# resolver_ad2s1210.net
KiCad netlist of a schematic drawn in Altium Designer
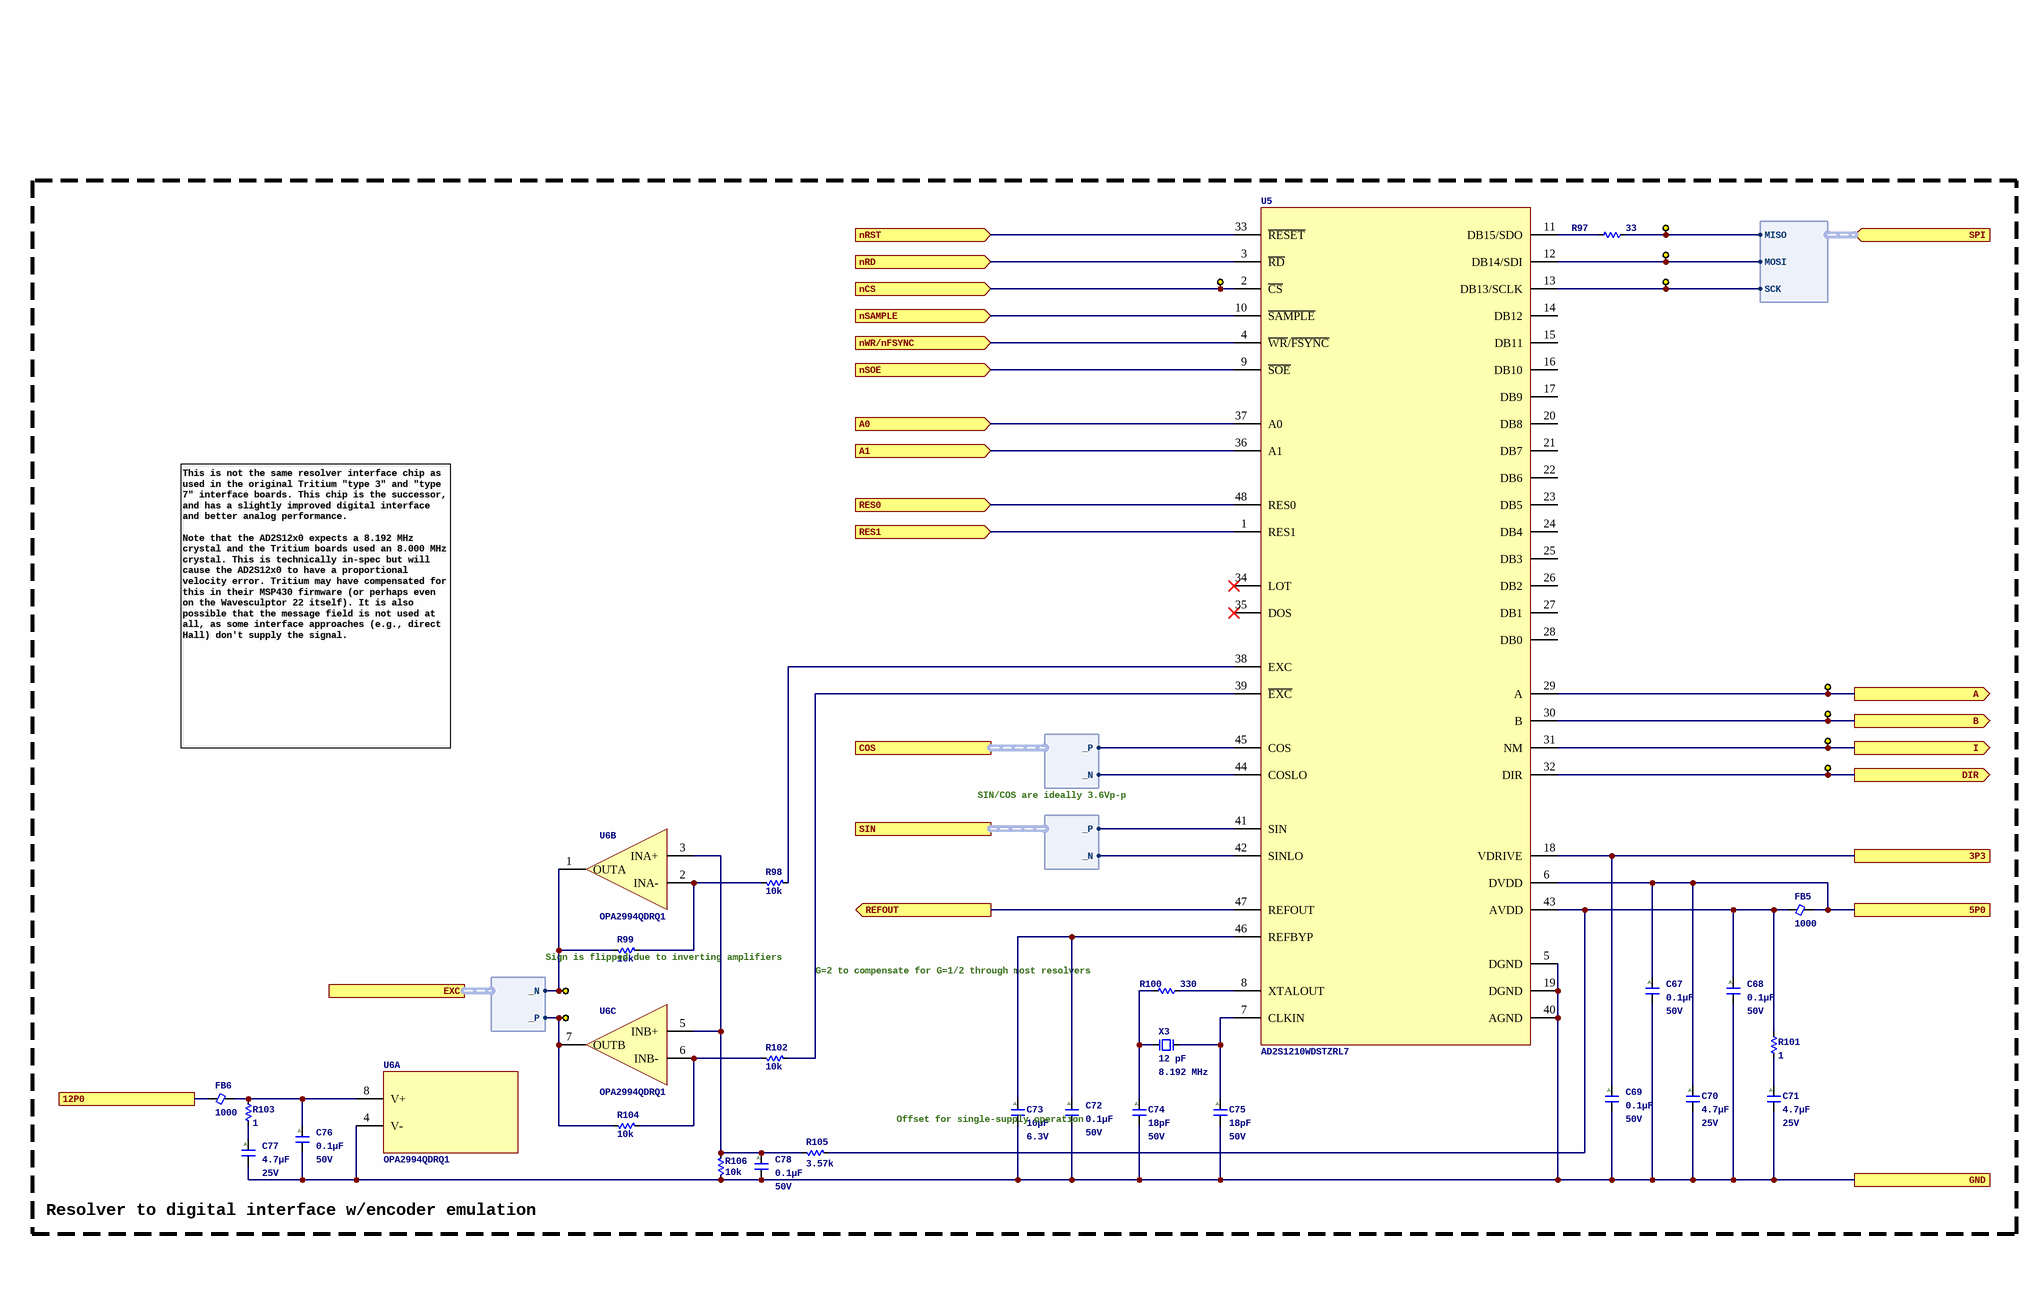
[diagram p0: resolver_ad2s1210.SchDoc]

(export (version "E")
  (design (tool "Eeschema 10.0.6"))
  (components
    (comp (ref "C67")
      (value "CGA2B3X7R1H104M050BB")
      (footprint "C0402_0.55MM")
      (description "CAP CER 0.1UF 50V X7R 0402")
      (fields
        (field (name "CAPACITANCE") "0.1µF")
        (field (name "VOLTAGE - RATED") "50V")
        (field (name "TOLERANCE") "±20%")
        (field (name "MANUFACTURER") "TDK Corporation")
      )
      (libsource (lib "sscp") (part "__template_cap_auto"))
    )
    (comp (ref "C68")
      (value "CGA2B3X7R1H104M050BB")
      (footprint "C0402_0.55MM")
      (description "CAP CER 0.1UF 50V X7R 0402")
      (fields
        (field (name "CAPACITANCE") "0.1µF")
        (field (name "VOLTAGE - RATED") "50V")
        (field (name "TOLERANCE") "±20%")
        (field (name "MANUFACTURER") "TDK Corporation")
      )
      (libsource (lib "sscp") (part "__template_cap_auto"))
    )
    (comp (ref "C69")
      (value "CGA2B3X7R1H104M050BB")
      (footprint "C0402_0.55MM")
      (description "CAP CER 0.1UF 50V X7R 0402")
      (fields
        (field (name "CAPACITANCE") "0.1µF")
        (field (name "VOLTAGE - RATED") "50V")
        (field (name "TOLERANCE") "±20%")
        (field (name "MANUFACTURER") "TDK Corporation")
      )
      (libsource (lib "sscp") (part "__template_cap_auto"))
    )
    (comp (ref "C70")
      (value "CGA4J1X7R1E475K125AC")
      (footprint "C0805_1.45MM")
      (description "CAP CER 4.7UF 25V X7R 0805")
      (fields
        (field (name "CAPACITANCE") "4.7µF")
        (field (name "VOLTAGE - RATED") "25V")
        (field (name "TOLERANCE") "±10%")
        (field (name "MANUFACTURER") "TDK Corporation")
      )
      (libsource (lib "sscp") (part "__template_cap_auto"))
    )
    (comp (ref "C71")
      (value "CGA4J1X7R1E475K125AC")
      (footprint "C0805_1.45MM")
      (description "CAP CER 4.7UF 25V X7R 0805")
      (fields
        (field (name "CAPACITANCE") "4.7µF")
        (field (name "VOLTAGE - RATED") "25V")
        (field (name "TOLERANCE") "±10%")
        (field (name "MANUFACTURER") "TDK Corporation")
      )
      (libsource (lib "sscp") (part "__template_cap_auto"))
    )
    (comp (ref "C72")
      (value "CGA2B3X7R1H104M050BB")
      (footprint "C0402_0.55MM")
      (description "CAP CER 0.1UF 50V X7R 0402")
      (fields
        (field (name "CAPACITANCE") "0.1µF")
        (field (name "VOLTAGE - RATED") "50V")
        (field (name "TOLERANCE") "±20%")
        (field (name "MANUFACTURER") "TDK Corporation")
      )
      (libsource (lib "sscp") (part "__template_cap_auto"))
    )
    (comp (ref "C73")
      (value "CGA4J1X7R0J106M125AC")
      (footprint "C0805_1.45MM")
      (description "CAP CER 10UF 6.3V X7R 0805")
      (fields
        (field (name "CAPACITANCE") "10µF")
        (field (name "VOLTAGE - RATED") "6.3V")
        (field (name "TOLERANCE") "±20%")
        (field (name "MANUFACTURER") "TDK Corporation")
      )
      (libsource (lib "sscp") (part "__template_cap_auto"))
    )
    (comp (ref "C74")
      (value "CGA2B2C0G1H180J050BA")
      (footprint "C0402_0.55MM")
      (description "CAP CER 18PF 50V C0G 0402")
      (fields
        (field (name "CAPACITANCE") "18pF")
        (field (name "VOLTAGE - RATED") "50V")
        (field (name "TOLERANCE") "±5%")
        (field (name "MANUFACTURER") "TDK Corporation")
      )
      (libsource (lib "sscp") (part "__template_cap_auto"))
    )
    (comp (ref "C75")
      (value "CGA2B2C0G1H180J050BA")
      (footprint "C0402_0.55MM")
      (description "CAP CER 18PF 50V C0G 0402")
      (fields
        (field (name "CAPACITANCE") "18pF")
        (field (name "VOLTAGE - RATED") "50V")
        (field (name "TOLERANCE") "±5%")
        (field (name "MANUFACTURER") "TDK Corporation")
      )
      (libsource (lib "sscp") (part "__template_cap_auto"))
    )
    (comp (ref "C76")
      (value "CGA2B3X7R1H104M050BB")
      (footprint "C0402_0.55MM")
      (description "CAP CER 0.1UF 50V X7R 0402")
      (fields
        (field (name "CAPACITANCE") "0.1µF")
        (field (name "VOLTAGE - RATED") "50V")
        (field (name "TOLERANCE") "±20%")
        (field (name "MANUFACTURER") "TDK Corporation")
      )
      (libsource (lib "sscp") (part "__template_cap_auto"))
    )
    (comp (ref "C77")
      (value "CGA4J1X7R1E475K125AC")
      (footprint "C0805_1.45MM")
      (description "CAP CER 4.7UF 25V X7R 0805")
      (fields
        (field (name "CAPACITANCE") "4.7µF")
        (field (name "VOLTAGE - RATED") "25V")
        (field (name "TOLERANCE") "±10%")
        (field (name "MANUFACTURER") "TDK Corporation")
      )
      (libsource (lib "sscp") (part "__template_cap_auto"))
    )
    (comp (ref "C78")
      (value "CGA2B3X7R1H104M050BB")
      (footprint "C0402_0.55MM")
      (description "CAP CER 0.1UF 50V X7R 0402")
      (fields
        (field (name "CAPACITANCE") "0.1µF")
        (field (name "VOLTAGE - RATED") "50V")
        (field (name "TOLERANCE") "±20%")
        (field (name "MANUFACTURER") "TDK Corporation")
      )
      (libsource (lib "sscp") (part "__template_cap_auto"))
    )
    (comp (ref "FB5")
      (value "MPZ2012S102AT000")
      (footprint "FB0805_1.05MM")
      (description "FERRITE BEAD 1 KOHM 0805 1LN")
      (fields
        (field (name "IMPEDANCE (OHMS @ 100MHZ)") "1000")
        (field (name "MANUFACTURER") "TDK Corporation")
      )
      (libsource (lib "sscp") (part "__template_ferrite"))
    )
    (comp (ref "FB6")
      (value "MPZ2012S102AT000")
      (footprint "FB0805_1.05MM")
      (description "FERRITE BEAD 1 KOHM 0805 1LN")
      (fields
        (field (name "IMPEDANCE (OHMS @ 100MHZ)") "1000")
        (field (name "MANUFACTURER") "TDK Corporation")
      )
      (libsource (lib "sscp") (part "__template_ferrite"))
    )
    (comp (ref "R97")
      (value "ERJ-2RKF33R0X")
      (footprint "R0402_0.40MM")
      (description "RES SMD 33 OHM 1% 1/10W 0402")
      (fields
        (field (name "RESISTANCE") "33")
        (field (name "TOLERANCE") "±1%")
        (field (name "MANUFACTURER") "Panasonic Electronic Components")
      )
      (libsource (lib "sscp") (part "__template_resistor"))
    )
    (comp (ref "R98")
      (value "ERJ-2RKF1002X")
      (footprint "R0402_0.40MM")
      (description "RES SMD 10K OHM 1% 1/10W 0402")
      (fields
        (field (name "RESISTANCE") "10k")
        (field (name "TOLERANCE") "±1%")
        (field (name "MANUFACTURER") "Panasonic Electronic Components")
      )
      (libsource (lib "sscp") (part "__template_resistor"))
    )
    (comp (ref "R99")
      (value "ERJ-2RKF1002X")
      (footprint "R0402_0.40MM")
      (description "RES SMD 10K OHM 1% 1/10W 0402")
      (fields
        (field (name "RESISTANCE") "10k")
        (field (name "TOLERANCE") "±1%")
        (field (name "MANUFACTURER") "Panasonic Electronic Components")
      )
      (libsource (lib "sscp") (part "__template_resistor"))
    )
    (comp (ref "R100")
      (value "ERJ-PA2F3300X")
      (footprint "R0402_0.40MM")
      (description "RES SMD 330 OHM 1% 1/5W 0402")
      (fields
        (field (name "RESISTANCE") "330")
        (field (name "TOLERANCE") "±1%")
        (field (name "MANUFACTURER") "Panasonic Electronic Components")
      )
      (libsource (lib "sscp") (part "__template_resistor"))
    )
    (comp (ref "R101")
      (value "ERJ-2BQF1R0X")
      (footprint "R0402_0.40MM")
      (description "RES SMD 1 OHM 1% 1/6W 0402")
      (fields
        (field (name "RESISTANCE") "1")
        (field (name "TOLERANCE") "±1%")
        (field (name "MANUFACTURER") "Panasonic Electronic Components")
      )
      (libsource (lib "sscp") (part "__template_resistor"))
    )
    (comp (ref "R102")
      (value "ERJ-2RKF1002X")
      (footprint "R0402_0.40MM")
      (description "RES SMD 10K OHM 1% 1/10W 0402")
      (fields
        (field (name "RESISTANCE") "10k")
        (field (name "TOLERANCE") "±1%")
        (field (name "MANUFACTURER") "Panasonic Electronic Components")
      )
      (libsource (lib "sscp") (part "__template_resistor"))
    )
    (comp (ref "R103")
      (value "ERJ-2BQF1R0X")
      (footprint "R0402_0.40MM")
      (description "RES SMD 1 OHM 1% 1/6W 0402")
      (fields
        (field (name "RESISTANCE") "1")
        (field (name "TOLERANCE") "±1%")
        (field (name "MANUFACTURER") "Panasonic Electronic Components")
      )
      (libsource (lib "sscp") (part "__template_resistor"))
    )
    (comp (ref "R104")
      (value "ERJ-2RKF1002X")
      (footprint "R0402_0.40MM")
      (description "RES SMD 10K OHM 1% 1/10W 0402")
      (fields
        (field (name "RESISTANCE") "10k")
        (field (name "TOLERANCE") "±1%")
        (field (name "MANUFACTURER") "Panasonic Electronic Components")
      )
      (libsource (lib "sscp") (part "__template_resistor"))
    )
    (comp (ref "R105")
      (value "ERJ-2RKF3571X")
      (footprint "R0402_0.40MM")
      (description "RES SMD 3.57K OHM 1% 1/10W 0402")
      (fields
        (field (name "RESISTANCE") "3.57k")
        (field (name "TOLERANCE") "±1%")
        (field (name "MANUFACTURER") "Panasonic Electronic Components")
      )
      (libsource (lib "sscp") (part "__template_resistor"))
    )
    (comp (ref "R106")
      (value "ERJ-2RKF1002X")
      (footprint "R0402_0.40MM")
      (description "RES SMD 10K OHM 1% 1/10W 0402")
      (fields
        (field (name "RESISTANCE") "10k")
        (field (name "TOLERANCE") "±1%")
        (field (name "MANUFACTURER") "Panasonic Electronic Components")
      )
      (libsource (lib "sscp") (part "__template_resistor"))
    )
    (comp (ref "TP5")
      (value "~")
      (footprint "TP_GRABBY")
      (description "EMBEDDED TEST POINT FOR SALEAE TEST CLIPS")
      (libsource (lib "SSCP") (part "TEST_GRABBER"))
    )
    (comp (ref "TP6")
      (value "~")
      (footprint "TP_GRABBY")
      (description "EMBEDDED TEST POINT FOR SALEAE TEST CLIPS")
      (libsource (lib "SSCP") (part "TEST_GRABBER"))
    )
    (comp (ref "TP7")
      (value "~")
      (footprint "TP_GRABBY")
      (description "EMBEDDED TEST POINT FOR SALEAE TEST CLIPS")
      (libsource (lib "SSCP") (part "TEST_GRABBER"))
    )
    (comp (ref "TP18")
      (value "~")
      (footprint "TP_GRABBY")
      (description "EMBEDDED TEST POINT FOR SALEAE TEST CLIPS")
      (libsource (lib "SSCP") (part "TEST_GRABBER"))
    )
    (comp (ref "TP19")
      (value "~")
      (footprint "TP_GRABBY")
      (description "EMBEDDED TEST POINT FOR SALEAE TEST CLIPS")
      (libsource (lib "SSCP") (part "TEST_GRABBER"))
    )
    (comp (ref "TP20")
      (value "~")
      (footprint "TP_GRABBY")
      (description "EMBEDDED TEST POINT FOR SALEAE TEST CLIPS")
      (libsource (lib "SSCP") (part "TEST_GRABBER"))
    )
    (comp (ref "TP21")
      (value "~")
      (footprint "TP_GRABBY")
      (description "EMBEDDED TEST POINT FOR SALEAE TEST CLIPS")
      (libsource (lib "SSCP") (part "TEST_GRABBER"))
    )
    (comp (ref "TP22")
      (value "~")
      (footprint "TP_GRABBY")
      (description "EMBEDDED TEST POINT FOR SALEAE TEST CLIPS")
      (libsource (lib "SSCP") (part "TEST_GRABBER"))
    )
    (comp (ref "TP23")
      (value "RH-5002")
      (footprint "TP_RH-5002")
      (description "THT white clip turret")
      (fields (field (name "MANUFACTURER") "ronghe"))
      (libsource (lib "sscp") (part "__template_testpoint"))
    )
    (comp (ref "TP24")
      (value "RH-5002")
      (footprint "TP_RH-5002")
      (description "THT white clip turret")
      (fields (field (name "MANUFACTURER") "ronghe"))
      (libsource (lib "sscp") (part "__template_testpoint"))
    )
    (comp (ref "U5")
      (value "AD2S1210WDSTZRL7")
      (footprint "48TQFP7")
      (description "Synchro or Resolver to Digital Converter, PQFP44")
      (fields (field (name "MANUFACTURER") "Analog Devices"))
      (libsource (lib "SSCP") (part "RESOLVER_AD2S1210WDSTZ"))
    )
    (comp (ref "U6")
      (value "OPA2994QDRQ1")
      (footprint "8SOIC150")
      (description "Automotive, dual, 24V 25MHz high-output-current (150 mA) operational amplifier 8-SOIC -40 to 125")
      (fields (field (name "MANUFACTURER") "Texas Instruments"))
      (libsource (lib "") (part "OPAMP_OPA2994QDRQ1_1"))
    )
    (comp (ref "X3")
      (value "ECS-81.92-12-30Q-EN-TR")
      (footprint "XTAL_ECX-53Q")
      (description "Parallel - Fundamental Quartz Crystal, 8.192MHz Nom")
      (fields
        (field (name "MANUFACTURER") "ECS International")
        (field (name "LOAD CAPACITANCE") "12 pF")
        (field (name "FREQUENCY") "8.192 MHz")
      )
      (libsource (lib "SSCP") (part "XTAL_ECS-81.92-12-30Q-EN-TR"))
    )
  )
  (nets
    (net (code "3") (name "/3P3") (class "Default")
      (node (ref "C69") (pin "1") (pintype "passive"))
      (node (ref "U5") (pin "18") (pinfunction "VDRIVE_18") (pintype "passive"))
    )
    (net (code "4") (name "/5P0") (class "Default")
      (node (ref "C67") (pin "1") (pintype "passive"))
      (node (ref "C70") (pin "1") (pintype "passive"))
      (node (ref "FB5") (pin "2") (pintype "passive"))
      (node (ref "U5") (pin "6") (pinfunction "DVDD_6") (pintype "passive"))
    )
    (net (code "5") (name "/12P0") (class "Default") (node (ref "FB6") (pin "1") (pintype "passive")))
    (net (code "6") (name "/A") (class "Default")
      (node (ref "TP18") (pin "1") (pintype "passive"))
      (node (ref "U5") (pin "29") (pinfunction "A_29") (pintype "passive"))
    )
    (net (code "7") (name "/A0") (class "Default")
      (node (ref "U5") (pin "37") (pinfunction "A0_37") (pintype "passive"))
    )
    (net (code "8") (name "/A1") (class "Default")
      (node (ref "U5") (pin "36") (pinfunction "A1_36") (pintype "passive"))
    )
    (net (code "9") (name "/B") (class "Default")
      (node (ref "TP19") (pin "1") (pintype "passive"))
      (node (ref "U5") (pin "30") (pinfunction "B_30") (pintype "passive"))
    )
    (net (code "10") (name "/DIR") (class "Default")
      (node (ref "TP21") (pin "1") (pintype "passive"))
      (node (ref "U5") (pin "32") (pinfunction "DIR_32") (pintype "passive"))
    )
    (net (code "11") (name "/GND") (class "Default")
      (node (ref "C67") (pin "2") (pintype "passive"))
      (node (ref "C68") (pin "2") (pintype "passive"))
      (node (ref "C69") (pin "2") (pintype "passive"))
      (node (ref "C70") (pin "2") (pintype "passive"))
      (node (ref "C71") (pin "2") (pintype "passive"))
      (node (ref "C72") (pin "2") (pintype "passive"))
      (node (ref "C73") (pin "2") (pintype "passive"))
      (node (ref "C74") (pin "2") (pintype "passive"))
      (node (ref "C75") (pin "2") (pintype "passive"))
      (node (ref "C76") (pin "2") (pintype "passive"))
      (node (ref "C77") (pin "2") (pintype "passive"))
      (node (ref "C78") (pin "2") (pintype "passive"))
      (node (ref "R106") (pin "2") (pintype "passive"))
      (node (ref "U5") (pin "19") (pinfunction "DGND_19") (pintype "passive"))
      (node (ref "U5") (pin "40") (pinfunction "AGND_40") (pintype "passive"))
      (node (ref "U5") (pin "5") (pinfunction "DGND_5") (pintype "passive"))
      (node (ref "U6") (pin "4") (pinfunction "V-_4") (pintype "passive"))
    )
    (net (code "12") (name "/I") (class "Default")
      (node (ref "TP20") (pin "1") (pintype "passive"))
      (node (ref "U5") (pin "31") (pinfunction "NM_31") (pintype "passive"))
    )
    (net (code "13") (name "/MISO") (class "Default")
      (node (ref "R97") (pin "1") (pintype "passive"))
      (node (ref "TP5") (pin "1") (pintype "passive"))
    )
    (net (code "14") (name "/MOSI") (class "Default")
      (node (ref "TP6") (pin "1") (pintype "passive"))
      (node (ref "U5") (pin "12") (pinfunction "DB14/SDI_12") (pintype "passive"))
    )
    (net (code "15") (name "/REFOUT") (class "Default")
      (node (ref "U5") (pin "47") (pinfunction "REFOUT_47") (pintype "passive"))
    )
    (net (code "16") (name "/RES0") (class "Default")
      (node (ref "U5") (pin "48") (pinfunction "RES0_48") (pintype "passive"))
    )
    (net (code "17") (name "/RES1") (class "Default")
      (node (ref "U5") (pin "1") (pinfunction "RES1_1") (pintype "passive"))
    )
    (net (code "18") (name "/SCK") (class "Default")
      (node (ref "TP7") (pin "1") (pintype "passive"))
      (node (ref "U5") (pin "13") (pinfunction "DB13/SCLK_13") (pintype "passive"))
    )
    (net (code "19") (name "/nCS") (class "Default")
      (node (ref "TP22") (pin "1") (pintype "passive"))
      (node (ref "U5") (pin "2") (pinfunction "~{CS}_2") (pintype "passive"))
    )
    (net (code "20") (name "/nRD") (class "Default")
      (node (ref "U5") (pin "3") (pinfunction "~{RD}_3") (pintype "passive"))
    )
    (net (code "21") (name "/nRST") (class "Default")
      (node (ref "U5") (pin "33") (pinfunction "~{RESET}_33") (pintype "passive"))
    )
    (net (code "22") (name "/nSAMPLE") (class "Default")
      (node (ref "U5") (pin "10") (pinfunction "~{SAMPLE}_10") (pintype "passive"))
    )
    (net (code "23") (name "/nSOE") (class "Default")
      (node (ref "U5") (pin "9") (pinfunction "~{SOE}_9") (pintype "passive"))
    )
    (net (code "24") (name "/nWR{slash}nFSYNC") (class "Default")
      (node (ref "U5") (pin "4") (pinfunction "~{WR}/~{FSYNC}_4") (pintype "passive"))
    )
    (net (code "27") (name "Net-(C71-Pad1)") (class "Default")
      (node (ref "C71") (pin "1") (pintype "passive"))
      (node (ref "R101") (pin "1") (pintype "passive"))
    )
    (net (code "28") (name "Net-(C74-Pad1)") (class "Default")
      (node (ref "C74") (pin "1") (pintype "passive"))
      (node (ref "R100") (pin "1") (pintype "passive"))
      (node (ref "X3") (pin "1") (pinfunction "1_1") (pintype "passive"))
    )
    (net (code "29") (name "Net-(C77-Pad1)") (class "Default")
      (node (ref "C77") (pin "1") (pintype "passive"))
      (node (ref "R103") (pin "1") (pintype "passive"))
    )
    (net (code "30") (name "Net-(U5-AVDD)") (class "Default")
      (node (ref "C68") (pin "1") (pintype "passive"))
      (node (ref "FB5") (pin "1") (pintype "passive"))
      (node (ref "R101") (pin "2") (pintype "passive"))
      (node (ref "R105") (pin "2") (pintype "passive"))
      (node (ref "U5") (pin "43") (pinfunction "AVDD_43") (pintype "passive"))
    )
    (net (code "31") (name "Net-(U5-CLKIN)") (class "Default")
      (node (ref "C75") (pin "1") (pintype "passive"))
      (node (ref "U5") (pin "7") (pinfunction "CLKIN_7") (pintype "passive"))
      (node (ref "X3") (pin "2") (pinfunction "2_2") (pintype "passive"))
    )
    (net (code "32") (name "Net-(U5-DB15{slash}SDO)") (class "Default")
      (node (ref "R97") (pin "2") (pintype "passive"))
      (node (ref "U5") (pin "11") (pinfunction "DB15/SDO_11") (pintype "passive"))
    )
    (net (code "33") (name "Net-(U5-EXC)") (class "Default")
      (node (ref "R98") (pin "2") (pintype "passive"))
      (node (ref "U5") (pin "38") (pinfunction "EXC_38") (pintype "passive"))
    )
    (net (code "34") (name "Net-(U5-REFBYP)") (class "Default")
      (node (ref "C72") (pin "1") (pintype "passive"))
      (node (ref "C73") (pin "1") (pintype "passive"))
      (node (ref "U5") (pin "46") (pinfunction "REFBYP_46") (pintype "passive"))
    )
    (net (code "35") (name "Net-(U5-XTALOUT)") (class "Default")
      (node (ref "R100") (pin "2") (pintype "passive"))
      (node (ref "U5") (pin "8") (pinfunction "XTALOUT_8") (pintype "passive"))
    )
    (net (code "36") (name "Net-(U5-~{EXC})") (class "Default")
      (node (ref "R102") (pin "2") (pintype "passive"))
      (node (ref "U5") (pin "39") (pinfunction "~{EXC}_39") (pintype "passive"))
    )
    (net (code "37") (name "Net-(U6A-V+)") (class "Default")
      (node (ref "C76") (pin "1") (pintype "passive"))
      (node (ref "FB6") (pin "2") (pintype "passive"))
      (node (ref "R103") (pin "2") (pintype "passive"))
      (node (ref "U6") (pin "8") (pinfunction "V+_8") (pintype "passive"))
    )
    (net (code "38") (name "Net-(U6B-INA+)") (class "Default")
      (node (ref "C78") (pin "1") (pintype "passive"))
      (node (ref "R105") (pin "1") (pintype "passive"))
      (node (ref "R106") (pin "1") (pintype "passive"))
      (node (ref "U6") (pin "3") (pinfunction "INA+_3") (pintype "passive"))
      (node (ref "U6") (pin "5") (pinfunction "INB+_5") (pintype "passive"))
    )
    (net (code "39") (name "Net-(U6B-INA-)") (class "Default")
      (node (ref "R98") (pin "1") (pintype "passive"))
      (node (ref "R99") (pin "2") (pintype "passive"))
      (node (ref "U6") (pin "2") (pinfunction "INA-_2") (pintype "passive"))
    )
    (net (code "40") (name "Net-(U6B-OUTA)") (class "Default")
      (node (ref "R99") (pin "1") (pintype "passive"))
      (node (ref "TP23") (pin "1") (pintype "passive"))
      (node (ref "U6") (pin "1") (pinfunction "OUTA_1") (pintype "passive"))
    )
    (net (code "41") (name "Net-(U6C-INB-)") (class "Default")
      (node (ref "R102") (pin "1") (pintype "passive"))
      (node (ref "R104") (pin "2") (pintype "passive"))
      (node (ref "U6") (pin "6") (pinfunction "INB-_6") (pintype "passive"))
    )
    (net (code "42") (name "Net-(U6C-OUTB)") (class "Default")
      (node (ref "R104") (pin "1") (pintype "passive"))
      (node (ref "TP24") (pin "1") (pintype "passive"))
      (node (ref "U6") (pin "7") (pinfunction "OUTB_7") (pintype "passive"))
    )
    (net (code "43") (name "unconnected-(U5-COS-Pad45)") (class "Default")
      (node (ref "U5") (pin "45") (pinfunction "COS_45") (pintype "passive"))
    )
    (net (code "44") (name "unconnected-(U5-COSLO-Pad44)") (class "Default")
      (node (ref "U5") (pin "44") (pinfunction "COSLO_44") (pintype "passive"))
    )
    (net (code "45") (name "unconnected-(U5-DB0-Pad28)") (class "Default")
      (node (ref "U5") (pin "28") (pinfunction "DB0_28") (pintype "passive"))
    )
    (net (code "46") (name "unconnected-(U5-DB1-Pad27)") (class "Default")
      (node (ref "U5") (pin "27") (pinfunction "DB1_27") (pintype "passive"))
    )
    (net (code "47") (name "unconnected-(U5-DB2-Pad26)") (class "Default")
      (node (ref "U5") (pin "26") (pinfunction "DB2_26") (pintype "passive"))
    )
    (net (code "48") (name "unconnected-(U5-DB3-Pad25)") (class "Default")
      (node (ref "U5") (pin "25") (pinfunction "DB3_25") (pintype "passive"))
    )
    (net (code "49") (name "unconnected-(U5-DB4-Pad24)") (class "Default")
      (node (ref "U5") (pin "24") (pinfunction "DB4_24") (pintype "passive"))
    )
    (net (code "50") (name "unconnected-(U5-DB5-Pad23)") (class "Default")
      (node (ref "U5") (pin "23") (pinfunction "DB5_23") (pintype "passive"))
    )
    (net (code "51") (name "unconnected-(U5-DB6-Pad22)") (class "Default")
      (node (ref "U5") (pin "22") (pinfunction "DB6_22") (pintype "passive"))
    )
    (net (code "52") (name "unconnected-(U5-DB7-Pad21)") (class "Default")
      (node (ref "U5") (pin "21") (pinfunction "DB7_21") (pintype "passive"))
    )
    (net (code "53") (name "unconnected-(U5-DB8-Pad20)") (class "Default")
      (node (ref "U5") (pin "20") (pinfunction "DB8_20") (pintype "passive"))
    )
    (net (code "54") (name "unconnected-(U5-DB9-Pad17)") (class "Default")
      (node (ref "U5") (pin "17") (pinfunction "DB9_17") (pintype "passive"))
    )
    (net (code "55") (name "unconnected-(U5-DB10-Pad16)") (class "Default")
      (node (ref "U5") (pin "16") (pinfunction "DB10_16") (pintype "passive"))
    )
    (net (code "56") (name "unconnected-(U5-DB11-Pad15)") (class "Default")
      (node (ref "U5") (pin "15") (pinfunction "DB11_15") (pintype "passive"))
    )
    (net (code "57") (name "unconnected-(U5-DB12-Pad14)") (class "Default")
      (node (ref "U5") (pin "14") (pinfunction "DB12_14") (pintype "passive"))
    )
    (net (code "58") (name "unconnected-(U5-DOS-Pad35)") (class "Default")
      (node (ref "U5") (pin "35") (pinfunction "DOS_35") (pintype "passive+no_connect"))
    )
    (net (code "59") (name "unconnected-(U5-LOT-Pad34)") (class "Default")
      (node (ref "U5") (pin "34") (pinfunction "LOT_34") (pintype "passive+no_connect"))
    )
    (net (code "60") (name "unconnected-(U5-SIN-Pad41)") (class "Default")
      (node (ref "U5") (pin "41") (pinfunction "SIN_41") (pintype "passive"))
    )
    (net (code "61") (name "unconnected-(U5-SINLO-Pad42)") (class "Default")
      (node (ref "U5") (pin "42") (pinfunction "SINLO_42") (pintype "passive"))
    )
  )
)
